# 5V_power.net
KiCad netlist of a schematic drawn in Altium Designer
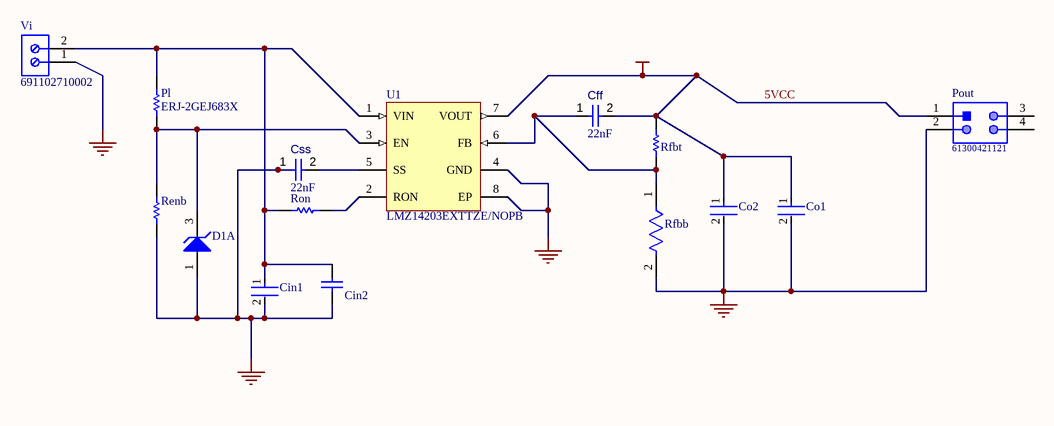
[diagram p0: 5V_power.SchDoc]

(export (version "E")
  (design (tool "Eeschema 10.0.6"))
  (components
    (comp (ref "Cff")
      (value "22nF")
      (footprint "FP-C0805C-DN-MFG")
      (description "Chip Capacitor, 22nF +/-20%, 10V, 0402, Thickness 0.6 mm")
      (fields (field (name "TOLERANCE") "10%") (field (name "Comment") "C0805C223K5RACTU"))
      (libsource (lib "Erik Huuki PCB designs") (part "CAP-NP-2"))
    )
    (comp (ref "Cin1")
      (value "CC0603KRX7R5BB105")
      (footprint "FP-CC0603-DA-MFG")
      (description "0603 1 uF 6.3 V ±10 % Tolerance X7R SMT Multilayer Ceramic Capacitor")
      (fields
        (field (name "OCTOPART") "https://octopart.com/cc0603krx7r5bb105-yageo-11543596")
        (field (name "TOLERANCE") "0.1")
      )
      (libsource (lib "Altium Content Vault") (part "11868f565c42a9108669ba33697ecf6"))
    )
    (comp (ref "Cin2")
      (value "CAP 10uF 25V 1206(3216)")
      (footprint "CAPC1206(3216)190_N")
      (description "CAP 10uF 25V -20% to +80% 1206 (3216 Metric) Thickness 1.9mm SMD")
      (fields (field (name "TOLERANCE") "-20% to +80%"))
      (libsource (lib "Altium Content Vault") (part "CAP"))
    )
    (comp (ref "Co1")
      (value "CC0603KRX7R5BB105")
      (footprint "FP-CC0603-DA-MFG")
      (description "0603 1 uF 6.3 V ±10 % Tolerance X7R SMT Multilayer Ceramic Capacitor")
      (fields
        (field (name "OCTOPART") "https://octopart.com/cc0603krx7r5bb105-yageo-11543596")
        (field (name "TOLERANCE") "0.1")
      )
      (libsource (lib "Altium Content Vault") (part "11868f565c42a9108669ba33697ecf6"))
    )
    (comp (ref "Co2")
      (value "CL32A107MQVNNNE")
      (footprint "FP-CL32-IPC_C")
      (description "CAP CER 100UF 6.3V X5R 1210")
      (fields (field (name "VOLTAGE") "6.3V") (field (name "TOLERANCE") "20%"))
      (libsource (lib "Altium Content Vault") (part "b4654b650e69147ec39a6b967a45e02"))
    )
    (comp (ref "Css")
      (value "22nF")
      (footprint "FP-C0805C-DN-MFG")
      (description "Chip Capacitor, 22nF +/-20%, 10V, 0402, Thickness 0.6 mm")
      (fields (field (name "TOLERANCE") "10%") (field (name "Comment") "C0805C223K5RACTU"))
      (libsource (lib "Erik Huuki PCB designs") (part "CAP-NP-2"))
    )
    (comp (ref "D1")
      (value "MMBZ5231BLT1G")
      (footprint "ONSC-SOT-23-3-318-08_V")
      (description "Zener Voltage Regulator, 225 mW, 3-Pin SOT-23, Pb-Free, Tape and Reel")
      (fields (field (name "MANUFACTURER") "On Semiconductor"))
      (libsource (lib "Altium Content Vault") (part "ONSC-A1K3-3"))
    )
    (comp (ref "Pl")
      (value "ERJ-2GEJ683X")
      (footprint "RESC1005X40X25LL05T05")
      (fields (field (name "MANUFACTURER") "Panasonic"))
      (libsource (lib "Altium Content Vault") (part "RES"))
    )
    (comp (ref "Pout")
      (value "61300421121")
      (footprint "61300421121")
      (description "THT Vertical Pin Header WR-PHD, Pitch 2.54 mm, Dual Row, 4 pins")
      (fields (field (name "MANUFACTURER") "Wurth Elektronik") (field (name "PUBLISHER") "WurthElektronik"))
      (libsource (lib "Altium Content Vault") (part "WE-CN-2P-M-R4"))
    )
    (comp (ref "Renb")
      (value "ERJ-3EKF1182V")
      (footprint "RESC1608X55X30LL15T15")
      (fields (field (name "MANUFACTURER") "Panasonic"))
      (libsource (lib "Altium Content Vault") (part "RES"))
    )
    (comp (ref "Rfbb")
      (value "RP73PF1J1K07BTDF")
      (footprint "FP-RP73P-1J-MFG")
      (description "RES SMD 1.07K OHM 0.1% 1/6W 0603")
      (fields
        (field (name "MANUFACTURER") "TE Connectivity")
        (field (name "OCTOPART") "https://octopart.com/rp73pf1j1k07btdf-te+connectivity-45465727")
      )
      (libsource (lib "Altium Content Vault") (part "1029c3af85768c4190bb7ad29bc67b5"))
    )
    (comp (ref "Rfbt")
      (value "CRCW02015K62FNED")
      (footprint "RESC0603X28X15NL05T05")
      (description "5.62k")
      (fields (field (name "MANUFACTURER") "Vishay Dale"))
      (libsource (lib "Altium Content Vault") (part "RES"))
    )
    (comp (ref "Ron")
      (value "CRCW0201100KJNED")
      (footprint "RESC0603X28X15NL05T05")
      (description "100k")
      (fields (field (name "MANUFACTURER") "Vishay"))
      (libsource (lib "Altium Content Vault") (part "RES"))
    )
    (comp (ref "U1")
      (value "LMZ14203EXTTZE/NOPB")
      (footprint "TZA07A_V")
      (fields (field (name "MANUFACTURER") "National Semiconductor"))
      (libsource (lib "Altium Content Vault") (part "PM-REG-LMZ12003-8"))
    )
    (comp (ref "Vi")
      (value "691102710002")
      (footprint "691102710002")
      (description "Series 102 - 5.00 mm Horizontal Entry Modular with Pressure Clamp WR-TBL, 2 pin")
      (fields (field (name "MANUFACTURER") "Wurth Elektronik") (field (name "PUBLISHER") "WurthElektronik"))
      (libsource (lib "Altium Content Vault") (part "WE-CN-1P-F-TB2"))
    )
  )
  (nets
    (net (code "1") (name "+5") (class "Default")
      (node (ref "Cff") (pin "2") (pinfunction "2_2") (pintype "passive"))
      (node (ref "Co1") (pin "1") (pinfunction "1_1") (pintype "passive"))
      (node (ref "Co2") (pin "1") (pinfunction "1_1") (pintype "passive"))
      (node (ref "Pout") (pin "1") (pinfunction "1_1") (pintype "passive"))
      (node (ref "Rfbt") (pin "2") (pinfunction "2_2") (pintype "passive"))
      (node (ref "U1") (pin "7") (pinfunction "VOUT_7") (pintype "output"))
    )
    (net (code "2") (name "GND") (class "Default")
      (node (ref "Cin1") (pin "2") (pinfunction "2_2") (pintype "passive"))
      (node (ref "Cin2") (pin "1") (pinfunction "1_1") (pintype "passive"))
      (node (ref "Co1") (pin "2") (pinfunction "2_2") (pintype "passive"))
      (node (ref "Co2") (pin "2") (pinfunction "2_2") (pintype "passive"))
      (node (ref "Css") (pin "1") (pinfunction "1_1") (pintype "passive"))
      (node (ref "D1") (pin "1") (pinfunction "A_1") (pintype "passive"))
      (node (ref "Pout") (pin "2") (pinfunction "2_2") (pintype "passive"))
      (node (ref "Renb") (pin "1") (pinfunction "1_1") (pintype "passive"))
      (node (ref "Rfbb") (pin "2") (pinfunction "2_2") (pintype "passive"))
      (node (ref "U1") (pin "4") (pinfunction "GND_4") (pintype "power_in"))
      (node (ref "U1") (pin "8") (pinfunction "EP_8") (pintype "passive"))
      (node (ref "Vi") (pin "1") (pinfunction "1_1") (pintype "passive"))
    )
    (net (code "3") (name "Net-(D1A-K)") (class "Default")
      (node (ref "D1") (pin "3") (pinfunction "K_3") (pintype "passive"))
      (node (ref "Pl") (pin "1") (pinfunction "1_1") (pintype "passive"))
      (node (ref "Renb") (pin "2") (pinfunction "2_2") (pintype "passive"))
      (node (ref "U1") (pin "3") (pinfunction "EN_3") (pintype "input"))
    )
    (net (code "4") (name "Net-(U1-FB)") (class "Default")
      (node (ref "Cff") (pin "1") (pinfunction "1_1") (pintype "passive"))
      (node (ref "Rfbb") (pin "1") (pinfunction "1_1") (pintype "passive"))
      (node (ref "Rfbt") (pin "1") (pinfunction "1_1") (pintype "passive"))
      (node (ref "U1") (pin "6") (pinfunction "FB_6") (pintype "input"))
    )
    (net (code "5") (name "Net-(U1-RON)") (class "Default")
      (node (ref "Ron") (pin "2") (pinfunction "2_2") (pintype "passive"))
      (node (ref "U1") (pin "2") (pinfunction "RON_2") (pintype "passive"))
    )
    (net (code "6") (name "Net-(U1-SS)") (class "Default")
      (node (ref "Css") (pin "2") (pinfunction "2_2") (pintype "passive"))
      (node (ref "U1") (pin "5") (pinfunction "SS_5") (pintype "passive"))
    )
    (net (code "7") (name "Net-(U1-VIN)") (class "Default")
      (node (ref "Cin1") (pin "1") (pinfunction "1_1") (pintype "passive"))
      (node (ref "Cin2") (pin "2") (pinfunction "2_2") (pintype "passive"))
      (node (ref "Pl") (pin "2") (pinfunction "2_2") (pintype "passive"))
      (node (ref "Ron") (pin "1") (pinfunction "1_1") (pintype "passive"))
      (node (ref "U1") (pin "1") (pinfunction "VIN_1") (pintype "input"))
      (node (ref "Vi") (pin "2") (pinfunction "2_2") (pintype "passive"))
    )
    (net (code "8") (name "unconnected-(Pout-Pad3)") (class "Default")
      (node (ref "Pout") (pin "3") (pinfunction "3_3") (pintype "passive"))
    )
    (net (code "9") (name "unconnected-(Pout-Pad4)") (class "Default")
      (node (ref "Pout") (pin "4") (pinfunction "4_4") (pintype "passive"))
    )
  )
)
